# LAN.net
KiCad netlist of a schematic drawn in Altium Designer
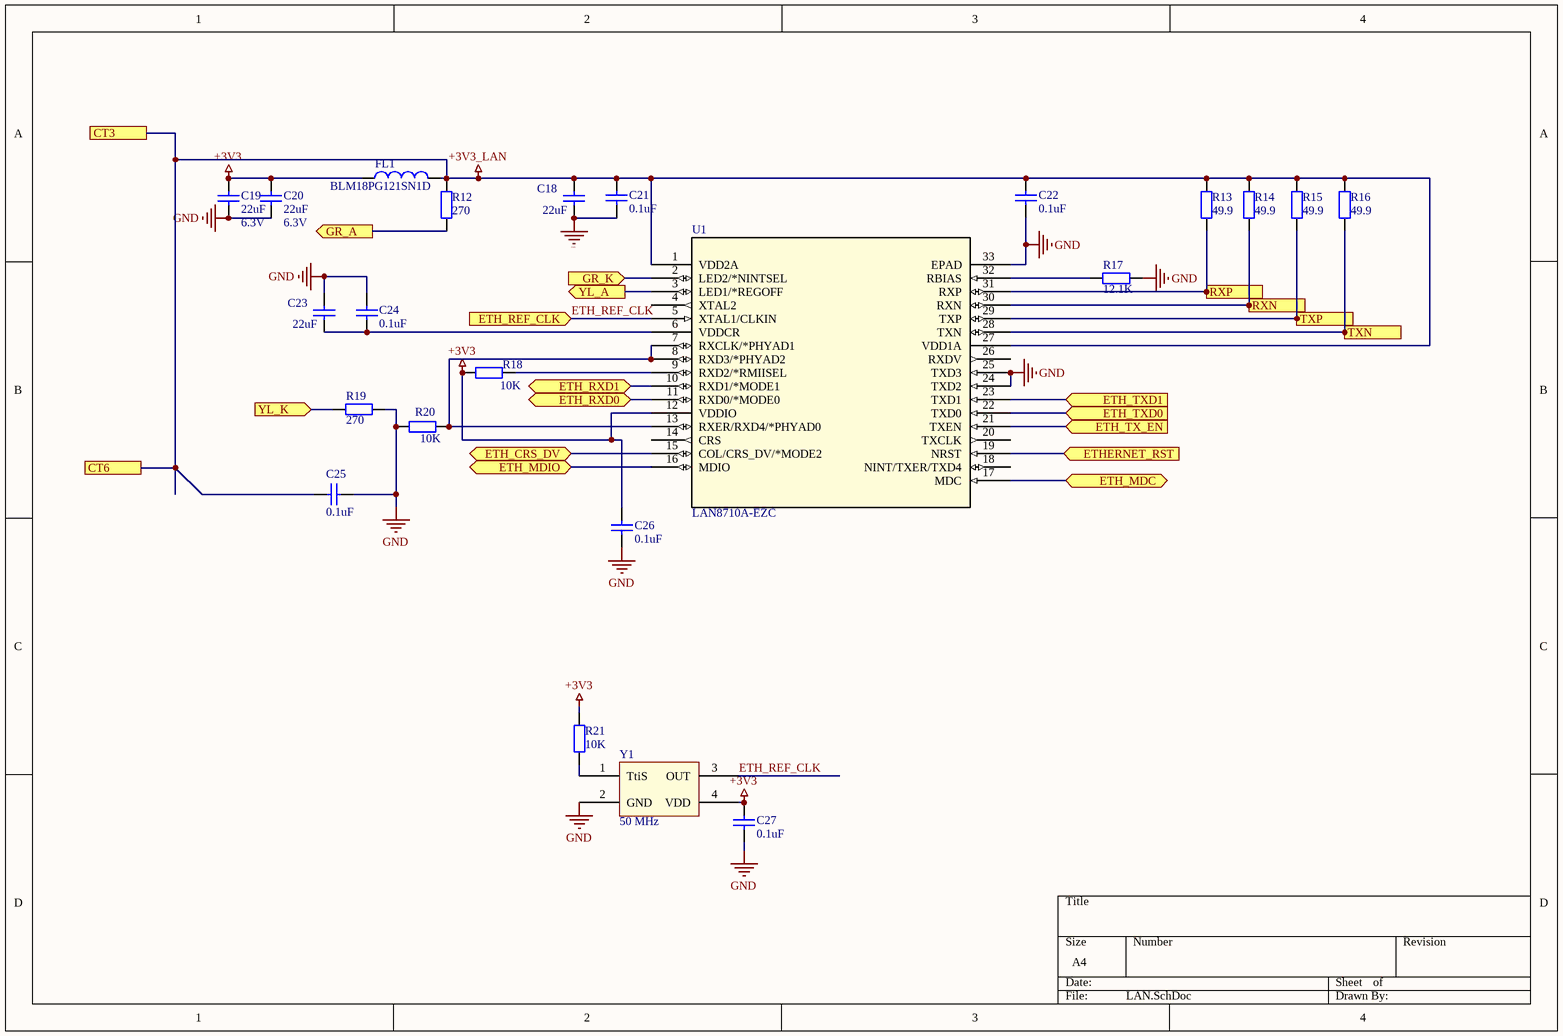
[diagram p0: LAN.SchDoc]

(export (version "E")
  (design (tool "Eeschema 10.0.6"))
  (components
    (comp (ref "C18")
      (value "22uF")
      (footprint "C0805")
      (description "Ceramic Capacitor")
      (fields (field (name "Comment") "C0805-22uF-10V-X5R"))
      (libsource (lib "Capacitors_SpekrtAT") (part "C0805-22uF-10V-X5R"))
    )
    (comp (ref "C19")
      (value "22uF")
      (footprint "C0603")
      (description "Ceramic Capacitor")
      (fields (field (name "VOLTAGE") "6.3V") (field (name "Comment") "C0603-22uF-6.3V-X5R"))
      (libsource (lib "Capacitors") (part "C0603-22uF-6.3V-X5R"))
    )
    (comp (ref "C20")
      (value "22uF")
      (footprint "C0603")
      (description "Ceramic Capacitor")
      (fields (field (name "VOLTAGE") "6.3V") (field (name "Comment") "C0603-22uF-6.3V-X5R"))
      (libsource (lib "Capacitors") (part "C0603-22uF-6.3V-X5R"))
    )
    (comp (ref "C21")
      (value "0.1uF")
      (footprint "C0603")
      (description "Ceramic Capacitor")
      (fields (field (name "Comment") "C0603-0.1uF-50V-X7R"))
      (libsource (lib "Capacitors_SpekrtAT") (part "C0603-0.1uF-50V-X7R"))
    )
    (comp (ref "C22")
      (value "0.1uF")
      (footprint "C0603")
      (description "Ceramic Capacitor")
      (fields (field (name "Comment") "C0603-0.1uF-50V-X7R"))
      (libsource (lib "Capacitors_SpekrtAT") (part "C0603-0.1uF-50V-X7R"))
    )
    (comp (ref "C23")
      (value "22uF")
      (footprint "C0805")
      (description "Ceramic Capacitor")
      (fields (field (name "Comment") "C0805-22uF-10V-X5R"))
      (libsource (lib "Capacitors_SpekrtAT") (part "C0805-22uF-10V-X5R"))
    )
    (comp (ref "C24")
      (value "0.1uF")
      (footprint "C0603")
      (description "Ceramic Capacitor")
      (fields (field (name "Comment") "C0603-0.1uF-50V-X7R"))
      (libsource (lib "Capacitors_SpekrtAT") (part "C0603-0.1uF-50V-X7R"))
    )
    (comp (ref "C25")
      (value "0.1uF")
      (footprint "C0603")
      (description "Ceramic Capacitor")
      (fields (field (name "Comment") "C0603-0.1uF-50V-X7R"))
      (libsource (lib "Capacitors_SpekrtAT") (part "C0603-0.1uF-50V-X7R"))
    )
    (comp (ref "C26")
      (value "0.1uF")
      (footprint "C0603")
      (description "Ceramic Capacitor")
      (fields (field (name "Comment") "C0603-0.1uF-50V-X7R"))
      (libsource (lib "Capacitors_SpekrtAT") (part "C0603-0.1uF-50V-X7R"))
    )
    (comp (ref "C27")
      (value "0.1uF")
      (footprint "C0603")
      (description "Ceramic Capacitor")
      (fields (field (name "Comment") "C0603-0.1uF-50V-X7R"))
      (libsource (lib "Capacitors_SpekrtAT") (part "C0603-0.1uF-50V-X7R"))
    )
    (comp (ref "FL1")
      (value "BLM18PG121SN1D")
      (footprint "BLM18AG102BH1D")
      (description "Filter")
      (fields (field (name "MOUSER PART NUMBER") "81-BLM18PG121SN1D"))
      (libsource (lib "SamacSys") (part "BLM18PG121SN1D"))
    )
    (comp (ref "R12")
      (value "270")
      (footprint "R0603")
      (description "Chip Resistor")
      (fields (field (name "Comment") "R0603-270-1%"))
      (libsource (lib "") (part "R0603-270-1%_1"))
    )
    (comp (ref "R13")
      (value "49.9")
      (footprint "R0603")
      (description "Chip Resistor")
      (fields (field (name "Comment") "R0603-49.9-1%"))
      (libsource (lib "Resistors") (part "R0603-49.9-1%"))
    )
    (comp (ref "R14")
      (value "49.9")
      (footprint "R0603")
      (description "Chip Resistor")
      (fields (field (name "Comment") "R0603-49.9-1%"))
      (libsource (lib "Resistors") (part "R0603-49.9-1%"))
    )
    (comp (ref "R15")
      (value "49.9")
      (footprint "R0603")
      (description "Chip Resistor")
      (fields (field (name "Comment") "R0603-49.9-1%"))
      (libsource (lib "Resistors") (part "R0603-49.9-1%"))
    )
    (comp (ref "R16")
      (value "49.9")
      (footprint "R0603")
      (description "Chip Resistor")
      (fields (field (name "Comment") "R0603-49.9-1%"))
      (libsource (lib "Resistors") (part "R0603-49.9-1%"))
    )
    (comp (ref "R17")
      (value "12.1K")
      (footprint "R0603")
      (description "Chip Resistor")
      (fields (field (name "Comment") "R0603-12.1K-1%"))
      (libsource (lib "Resistors") (part "R0603-12.1K-1%"))
    )
    (comp (ref "R18")
      (value "10K")
      (footprint "R0603")
      (description "Chip Resistor")
      (fields (field (name "Comment") "R0603-10K-1%"))
      (libsource (lib "") (part "R0603-10K-1%_1"))
    )
    (comp (ref "R19")
      (value "270")
      (footprint "R0603")
      (description "Chip Resistor")
      (fields (field (name "Comment") "R0603-270-1%"))
      (libsource (lib "Resistors") (part "R0603-270-1%"))
    )
    (comp (ref "R20")
      (value "10K")
      (footprint "R0603")
      (description "Chip Resistor")
      (fields (field (name "Comment") "R0603-10K-1%"))
      (libsource (lib "") (part "R0603-10K-1%_1"))
    )
    (comp (ref "R21")
      (value "10K")
      (footprint "R0603")
      (description "Chip Resistor")
      (fields (field (name "Comment") "R0603-10K-1%"))
      (libsource (lib "Resistors") (part "R0603-10K-1%"))
    )
    (comp (ref "U1")
      (value "LAN8710A-EZC")
      (footprint "QFN32_5X5MC_MCH")
      (fields (field (name "COPYRIGHT") "Copyright (C) 2018 Accelerated Designs. All rights reserved"))
      (libsource (lib "Panorama_V_0_0_1") (part "LAN8710A-EZC"))
    )
    (comp (ref "Y1")
      (value "50 MHz")
      (footprint "D7SX")
      (description "HXO-36B 50.000 HZ")
      (libsource (lib "Quartz") (part "HXO-36B 50.000 HZ"))
    )
  )
  (nets
    (net (code "1") (name "+3V3") (class "Default")
      (node (ref "C19") (pin "2") (pinfunction "2_2") (pintype "passive"))
      (node (ref "C20") (pin "2") (pinfunction "2_2") (pintype "passive"))
      (node (ref "C26") (pin "2") (pinfunction "2_2") (pintype "passive"))
      (node (ref "C27") (pin "2") (pinfunction "2_2") (pintype "passive"))
      (node (ref "FL1") (pin "1") (pinfunction "1_1") (pintype "passive"))
      (node (ref "R18") (pin "1") (pinfunction "1_1") (pintype "passive"))
      (node (ref "R21") (pin "2") (pinfunction "2_2") (pintype "passive"))
      (node (ref "U1") (pin "12") (pinfunction "VDDIO_12") (pintype "power_in"))
      (node (ref "Y1") (pin "4") (pinfunction "VDD_4") (pintype "passive"))
    )
    (net (code "2") (name "+3V3_LAN") (class "Default")
      (node (ref "C18") (pin "2") (pinfunction "2_2") (pintype "passive"))
      (node (ref "C21") (pin "1") (pinfunction "1_1") (pintype "passive"))
      (node (ref "C22") (pin "1") (pinfunction "1_1") (pintype "passive"))
      (node (ref "C25") (pin "2") (pinfunction "2_2") (pintype "passive"))
      (node (ref "FL1") (pin "2") (pinfunction "2_2") (pintype "passive"))
      (node (ref "R12") (pin "2") (pinfunction "2_2") (pintype "passive"))
      (node (ref "R13") (pin "2") (pinfunction "2_2") (pintype "passive"))
      (node (ref "R14") (pin "2") (pinfunction "2_2") (pintype "passive"))
      (node (ref "R15") (pin "2") (pinfunction "2_2") (pintype "passive"))
      (node (ref "R16") (pin "2") (pinfunction "2_2") (pintype "passive"))
      (node (ref "U1") (pin "1") (pinfunction "VDD2A_1") (pintype "power_in"))
      (node (ref "U1") (pin "27") (pinfunction "VDD1A_27") (pintype "power_in"))
    )
    (net (code "3") (name "/ETHERNET_RST") (class "Default")
      (node (ref "U1") (pin "19") (pinfunction "NRST_19") (pintype "input"))
    )
    (net (code "4") (name "/ETH_CRS_DV") (class "Default")
      (node (ref "U1") (pin "15") (pinfunction "COL/CRS_DV/*MODE2_15") (pintype "bidirectional"))
    )
    (net (code "5") (name "/ETH_MDC") (class "Default")
      (node (ref "U1") (pin "17") (pinfunction "MDC_17") (pintype "input"))
    )
    (net (code "6") (name "/ETH_MDIO") (class "Default")
      (node (ref "U1") (pin "16") (pinfunction "MDIO_16") (pintype "bidirectional"))
    )
    (net (code "7") (name "/ETH_REF_CLK") (class "Default")
      (node (ref "U1") (pin "5") (pinfunction "XTAL1/CLKIN_5") (pintype "input"))
      (node (ref "Y1") (pin "3") (pinfunction "OUT_3") (pintype "passive"))
    )
    (net (code "8") (name "/ETH_RXD0") (class "Default")
      (node (ref "U1") (pin "11") (pinfunction "RXD0/*MODE0_11") (pintype "bidirectional"))
    )
    (net (code "9") (name "/ETH_RXD1") (class "Default")
      (node (ref "U1") (pin "10") (pinfunction "RXD1/*MODE1_10") (pintype "bidirectional"))
    )
    (net (code "10") (name "/ETH_TXD0") (class "Default")
      (node (ref "U1") (pin "22") (pinfunction "TXD0_22") (pintype "input"))
    )
    (net (code "11") (name "/ETH_TXD1") (class "Default")
      (node (ref "U1") (pin "23") (pinfunction "TXD1_23") (pintype "input"))
    )
    (net (code "12") (name "/ETH_TX_EN") (class "Default")
      (node (ref "U1") (pin "21") (pinfunction "TXEN_21") (pintype "input"))
    )
    (net (code "13") (name "/GR_A") (class "Default")
      (node (ref "R12") (pin "1") (pinfunction "1_1") (pintype "passive"))
    )
    (net (code "14") (name "/GR_K") (class "Default")
      (node (ref "U1") (pin "2") (pinfunction "LED2/*NINTSEL_2") (pintype "bidirectional"))
    )
    (net (code "15") (name "/RXN") (class "Default")
      (node (ref "R14") (pin "1") (pinfunction "1_1") (pintype "passive"))
      (node (ref "U1") (pin "30") (pinfunction "RXN_30") (pintype "bidirectional"))
    )
    (net (code "16") (name "/RXP") (class "Default")
      (node (ref "R13") (pin "1") (pinfunction "1_1") (pintype "passive"))
      (node (ref "U1") (pin "31") (pinfunction "RXP_31") (pintype "bidirectional"))
    )
    (net (code "17") (name "/TXN") (class "Default")
      (node (ref "R16") (pin "1") (pinfunction "1_1") (pintype "passive"))
      (node (ref "U1") (pin "28") (pinfunction "TXN_28") (pintype "bidirectional"))
    )
    (net (code "18") (name "/TXP") (class "Default")
      (node (ref "R15") (pin "1") (pinfunction "1_1") (pintype "passive"))
      (node (ref "U1") (pin "29") (pinfunction "TXP_29") (pintype "bidirectional"))
    )
    (net (code "19") (name "/YL_A") (class "Default")
      (node (ref "U1") (pin "3") (pinfunction "LED1/*REGOFF_3") (pintype "bidirectional"))
    )
    (net (code "20") (name "/YL_K") (class "Default")
      (node (ref "R19") (pin "2") (pinfunction "2_2") (pintype "passive"))
    )
    (net (code "21") (name "GND") (class "Default")
      (node (ref "C18") (pin "1") (pinfunction "1_1") (pintype "passive"))
      (node (ref "C19") (pin "1") (pinfunction "1_1") (pintype "passive"))
      (node (ref "C20") (pin "1") (pinfunction "1_1") (pintype "passive"))
      (node (ref "C21") (pin "2") (pinfunction "2_2") (pintype "passive"))
      (node (ref "C22") (pin "2") (pinfunction "2_2") (pintype "passive"))
      (node (ref "C23") (pin "2") (pinfunction "2_2") (pintype "passive"))
      (node (ref "C24") (pin "2") (pinfunction "2_2") (pintype "passive"))
      (node (ref "C25") (pin "1") (pinfunction "1_1") (pintype "passive"))
      (node (ref "C26") (pin "1") (pinfunction "1_1") (pintype "passive"))
      (node (ref "C27") (pin "1") (pinfunction "1_1") (pintype "passive"))
      (node (ref "R17") (pin "2") (pinfunction "2_2") (pintype "passive"))
      (node (ref "R19") (pin "1") (pinfunction "1_1") (pintype "passive"))
      (node (ref "R20") (pin "1") (pinfunction "1_1") (pintype "passive"))
      (node (ref "U1") (pin "24") (pinfunction "TXD2_24") (pintype "input"))
      (node (ref "U1") (pin "25") (pinfunction "TXD3_25") (pintype "input"))
      (node (ref "U1") (pin "33") (pinfunction "EPAD_33") (pintype "passive"))
      (node (ref "Y1") (pin "2") (pinfunction "GND_2") (pintype "passive"))
    )
    (net (code "22") (name "Net-(U1-RBIAS)") (class "Default")
      (node (ref "R17") (pin "1") (pinfunction "1_1") (pintype "passive"))
      (node (ref "U1") (pin "32") (pinfunction "RBIAS_32") (pintype "input"))
    )
    (net (code "23") (name "Net-(U1-RXCLK{slash}*PHYAD1)") (class "Default")
      (node (ref "R20") (pin "2") (pinfunction "2_2") (pintype "passive"))
      (node (ref "U1") (pin "13") (pinfunction "RXER/RXD4/*PHYAD0_13") (pintype "bidirectional"))
      (node (ref "U1") (pin "7") (pinfunction "RXCLK/*PHYAD1_7") (pintype "bidirectional"))
      (node (ref "U1") (pin "8") (pinfunction "RXD3/*PHYAD2_8") (pintype "bidirectional"))
    )
    (net (code "24") (name "Net-(U1-RXD2{slash}*RMIISEL)") (class "Default")
      (node (ref "R18") (pin "2") (pinfunction "2_2") (pintype "passive"))
      (node (ref "U1") (pin "9") (pinfunction "RXD2/*RMIISEL_9") (pintype "bidirectional"))
    )
    (net (code "25") (name "Net-(U1-VDDCR)") (class "Default")
      (node (ref "C23") (pin "1") (pinfunction "1_1") (pintype "passive"))
      (node (ref "C24") (pin "1") (pinfunction "1_1") (pintype "passive"))
      (node (ref "U1") (pin "6") (pinfunction "VDDCR_6") (pintype "power_in"))
    )
    (net (code "26") (name "Net-(Y1-TtiS)") (class "Default")
      (node (ref "R21") (pin "1") (pinfunction "1_1") (pintype "passive"))
      (node (ref "Y1") (pin "1") (pinfunction "TtiS_1") (pintype "passive"))
    )
    (net (code "27") (name "unconnected-(U1-CRS-Pad14)") (class "Default")
      (node (ref "U1") (pin "14") (pinfunction "CRS_14") (pintype "output"))
    )
    (net (code "28") (name "unconnected-(U1-NINT{slash}TXER{slash}TXD4-Pad18)") (class "Default")
      (node (ref "U1") (pin "18") (pinfunction "NINT/TXER/TXD4_18") (pintype "bidirectional"))
    )
    (net (code "29") (name "unconnected-(U1-RXDV-Pad26)") (class "Default")
      (node (ref "U1") (pin "26") (pinfunction "RXDV_26") (pintype "output"))
    )
    (net (code "30") (name "unconnected-(U1-TXCLK-Pad20)") (class "Default")
      (node (ref "U1") (pin "20") (pinfunction "TXCLK_20") (pintype "output"))
    )
    (net (code "31") (name "unconnected-(U1-XTAL2-Pad4)") (class "Default")
      (node (ref "U1") (pin "4") (pinfunction "XTAL2_4") (pintype "output"))
    )
  )
)
